# Siren.net
KiCad netlist of a schematic drawn in EAGLE
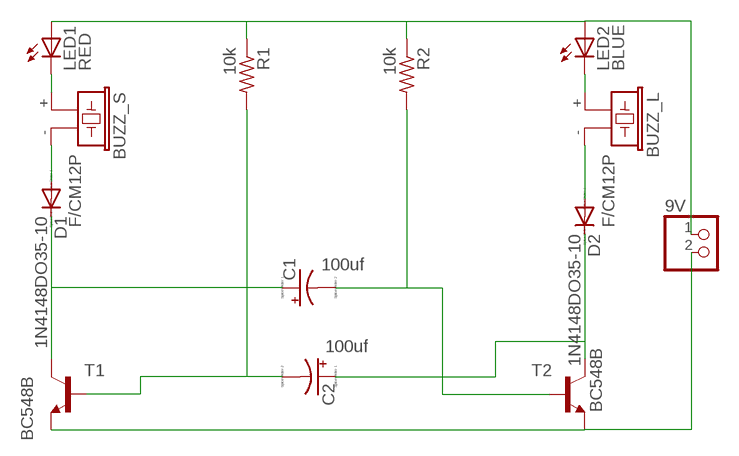
[diagram p0: schematic, sheet 1]

(export (version "E")
  (design (tool "Eeschema 10.0.6"))
  (components
    (comp (ref "9V")
      (value "PINHD-1X2")
      (footprint "eagle-import:1X02")
      (libsource (lib "eagle-import") (part "PINHD-1X2"))
    )
    (comp (ref "BUZZ_L")
      (value "F/CM12P")
      (footprint "eagle-import:F_CM12P")
      (libsource (lib "eagle-import") (part "F/CM12P"))
    )
    (comp (ref "BUZZ_S")
      (value "F/CM12P")
      (footprint "eagle-import:F_CM12P")
      (libsource (lib "eagle-import") (part "F/CM12P"))
    )
    (comp (ref "C1")
      (value "100uf")
      (footprint "eagle-import:E2,5-5")
      (libsource (lib "eagle-import") (part "CPOL-USE2.5-5"))
    )
    (comp (ref "C2")
      (value "100uf")
      (footprint "eagle-import:E2,5-5")
      (libsource (lib "eagle-import") (part "CPOL-USE2.5-5"))
    )
    (comp (ref "D1")
      (value "1N4148DO35-10")
      (footprint "eagle-import:DO35-10")
      (libsource (lib "eagle-import") (part "1N4148DO35-10"))
    )
    (comp (ref "D2")
      (value "1N4148DO35-10")
      (footprint "eagle-import:DO35-10")
      (libsource (lib "eagle-import") (part "1N4148DO35-10"))
    )
    (comp (ref "LED1")
      (value "RED")
      (footprint "eagle-import:LED5MM")
      (libsource (lib "eagle-import") (part "LED5MM"))
    )
    (comp (ref "LED2")
      (value "BLUE")
      (footprint "eagle-import:LED5MM")
      (libsource (lib "eagle-import") (part "LED5MM"))
    )
    (comp (ref "R1")
      (value "10k")
      (footprint "eagle-import:0204_7")
      (libsource (lib "eagle-import") (part "R-US_0204/7"))
    )
    (comp (ref "R2")
      (value "10k")
      (footprint "eagle-import:0204_7")
      (libsource (lib "eagle-import") (part "R-US_0204/7"))
    )
    (comp (ref "T1")
      (value "BC548B")
      (footprint "eagle-import:TO92-CBE")
      (libsource (lib "eagle-import") (part "-NPN-TO92-CBEBC548"))
    )
    (comp (ref "T2")
      (value "BC548B")
      (footprint "eagle-import:TO92-CBE")
      (libsource (lib "eagle-import") (part "-NPN-TO92-CBEBC548"))
    )
  )
  (nets
    (net (code "1") (name "Net-(9V-Pad1)") (class "Default")
      (node (ref "9V") (pin "1") (pinfunction "1_1") (pintype "passive"))
      (node (ref "LED1") (pin "A") (pinfunction "A_A") (pintype "passive"))
      (node (ref "LED2") (pin "A") (pinfunction "A_A") (pintype "passive"))
      (node (ref "R1") (pin "1") (pinfunction "1_1") (pintype "passive"))
      (node (ref "R2") (pin "1") (pinfunction "1_1") (pintype "passive"))
    )
    (net (code "2") (name "Net-(9V-Pad2)") (class "Default")
      (node (ref "9V") (pin "2") (pinfunction "2_2") (pintype "passive"))
      (node (ref "T1") (pin "E") (pinfunction "E_E") (pintype "passive"))
      (node (ref "T2") (pin "E") (pinfunction "E_E") (pintype "passive"))
    )
    (net (code "3") (name "Net-(BUZZ_L-1)") (class "Default")
      (node (ref "BUZZ_L") (pin "+") (pinfunction "1_+") (pintype "passive"))
      (node (ref "LED2") (pin "K") (pinfunction "C_K") (pintype "passive"))
    )
    (net (code "4") (name "Net-(BUZZ_L-2)") (class "Default")
      (node (ref "BUZZ_L") (pin "-") (pinfunction "2_-") (pintype "passive"))
      (node (ref "D2") (pin "A") (pinfunction "A_A") (pintype "passive"))
    )
    (net (code "5") (name "Net-(BUZZ_S-1)") (class "Default")
      (node (ref "BUZZ_S") (pin "+") (pinfunction "1_+") (pintype "passive"))
      (node (ref "LED1") (pin "K") (pinfunction "C_K") (pintype "passive"))
    )
    (net (code "6") (name "Net-(BUZZ_S-2)") (class "Default")
      (node (ref "BUZZ_S") (pin "-") (pinfunction "2_-") (pintype "passive"))
      (node (ref "D1") (pin "A") (pinfunction "A_A") (pintype "passive"))
    )
    (net (code "7") (name "Net-(C1-Pad+)") (class "Default")
      (node (ref "C1") (pin "+") (pinfunction "+_+") (pintype "passive"))
      (node (ref "D1") (pin "C") (pinfunction "C_C") (pintype "passive"))
      (node (ref "T1") (pin "C") (pinfunction "C_C") (pintype "passive"))
    )
    (net (code "8") (name "Net-(C1-Pad-)") (class "Default")
      (node (ref "C1") (pin "-") (pinfunction "-_-") (pintype "passive"))
      (node (ref "R2") (pin "2") (pinfunction "2_2") (pintype "passive"))
      (node (ref "T2") (pin "B") (pinfunction "B_B") (pintype "passive"))
    )
    (net (code "9") (name "Net-(C2-Pad+)") (class "Default")
      (node (ref "C2") (pin "+") (pinfunction "+_+") (pintype "passive"))
      (node (ref "D2") (pin "C") (pinfunction "C_C") (pintype "passive"))
      (node (ref "T2") (pin "C") (pinfunction "C_C") (pintype "passive"))
    )
    (net (code "10") (name "Net-(C2-Pad-)") (class "Default")
      (node (ref "C2") (pin "-") (pinfunction "-_-") (pintype "passive"))
      (node (ref "R1") (pin "2") (pinfunction "2_2") (pintype "passive"))
      (node (ref "T1") (pin "B") (pinfunction "B_B") (pintype "passive"))
    )
  )
)
